# W061X.net
KiCad netlist of a schematic drawn in EAGLE
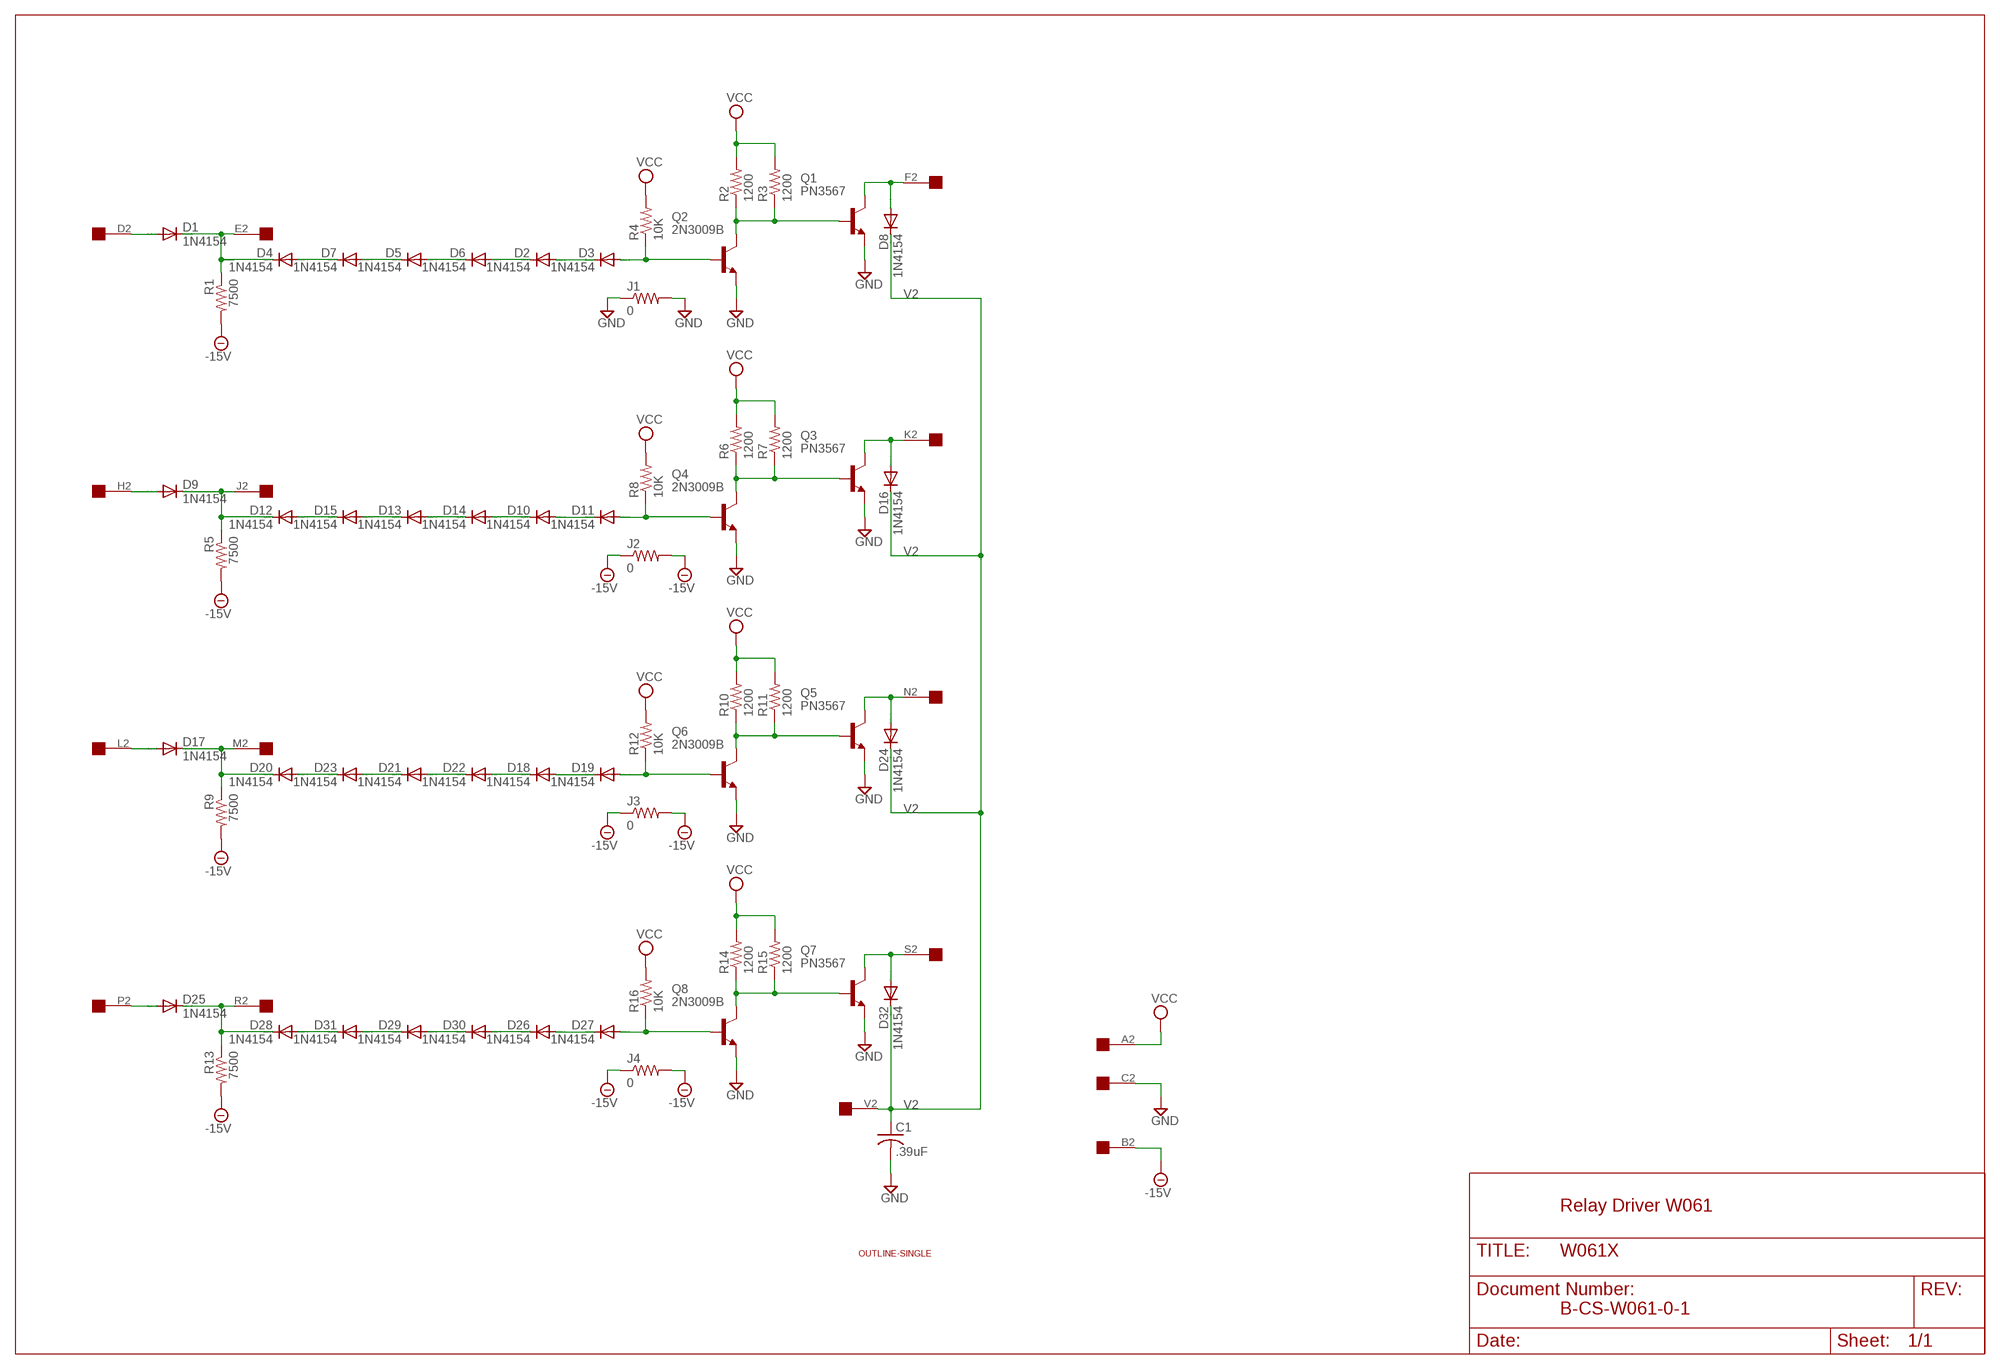
[diagram p0: schematic, sheet 1]

(export (version "E")
  (design (tool "Eeschema 10.0.6"))
  (components
    (comp (ref "C1")
      (value ".39uF")
      (footprint "eagle-import:C375-155X418")
      (libsource (lib "eagle-import") (part "C-US375-155X418"))
    )
    (comp (ref "D1")
      (value "1N4154")
      (footprint "eagle-import:DO35-10")
      (libsource (lib "eagle-import") (part "DIODE-DO35-10"))
    )
    (comp (ref "D2")
      (value "1N4154")
      (footprint "eagle-import:DO35-10")
      (libsource (lib "eagle-import") (part "DIODE-DO35-10"))
    )
    (comp (ref "D3")
      (value "1N4154")
      (footprint "eagle-import:DO35-10")
      (libsource (lib "eagle-import") (part "DIODE-DO35-10"))
    )
    (comp (ref "D4")
      (value "1N4154")
      (footprint "eagle-import:DO35-10")
      (libsource (lib "eagle-import") (part "DIODE-DO35-10"))
    )
    (comp (ref "D5")
      (value "1N4154")
      (footprint "eagle-import:DO35-10")
      (libsource (lib "eagle-import") (part "DIODE-DO35-10"))
    )
    (comp (ref "D6")
      (value "1N4154")
      (footprint "eagle-import:DO35-10")
      (libsource (lib "eagle-import") (part "DIODE-DO35-10"))
    )
    (comp (ref "D7")
      (value "1N4154")
      (footprint "eagle-import:DO35-10")
      (libsource (lib "eagle-import") (part "DIODE-DO35-10"))
    )
    (comp (ref "D8")
      (value "1N4154")
      (footprint "eagle-import:DO35-10")
      (libsource (lib "eagle-import") (part "DIODE-DO35-10"))
    )
    (comp (ref "D9")
      (value "1N4154")
      (footprint "eagle-import:DO35-10")
      (libsource (lib "eagle-import") (part "DIODE-DO35-10"))
    )
    (comp (ref "D10")
      (value "1N4154")
      (footprint "eagle-import:DO35-10")
      (libsource (lib "eagle-import") (part "DIODE-DO35-10"))
    )
    (comp (ref "D11")
      (value "1N4154")
      (footprint "eagle-import:DO35-10")
      (libsource (lib "eagle-import") (part "DIODE-DO35-10"))
    )
    (comp (ref "D12")
      (value "1N4154")
      (footprint "eagle-import:DO35-10")
      (libsource (lib "eagle-import") (part "DIODE-DO35-10"))
    )
    (comp (ref "D13")
      (value "1N4154")
      (footprint "eagle-import:DO35-10")
      (libsource (lib "eagle-import") (part "DIODE-DO35-10"))
    )
    (comp (ref "D14")
      (value "1N4154")
      (footprint "eagle-import:DO35-10")
      (libsource (lib "eagle-import") (part "DIODE-DO35-10"))
    )
    (comp (ref "D15")
      (value "1N4154")
      (footprint "eagle-import:DO35-10")
      (libsource (lib "eagle-import") (part "DIODE-DO35-10"))
    )
    (comp (ref "D16")
      (value "1N4154")
      (footprint "eagle-import:DO35-10")
      (libsource (lib "eagle-import") (part "DIODE-DO35-10"))
    )
    (comp (ref "D17")
      (value "1N4154")
      (footprint "eagle-import:DO35-10")
      (libsource (lib "eagle-import") (part "DIODE-DO35-10"))
    )
    (comp (ref "D18")
      (value "1N4154")
      (footprint "eagle-import:DO35-10")
      (libsource (lib "eagle-import") (part "DIODE-DO35-10"))
    )
    (comp (ref "D19")
      (value "1N4154")
      (footprint "eagle-import:DO35-10")
      (libsource (lib "eagle-import") (part "DIODE-DO35-10"))
    )
    (comp (ref "D20")
      (value "1N4154")
      (footprint "eagle-import:DO35-10")
      (libsource (lib "eagle-import") (part "DIODE-DO35-10"))
    )
    (comp (ref "D21")
      (value "1N4154")
      (footprint "eagle-import:DO35-10")
      (libsource (lib "eagle-import") (part "DIODE-DO35-10"))
    )
    (comp (ref "D22")
      (value "1N4154")
      (footprint "eagle-import:DO35-10")
      (libsource (lib "eagle-import") (part "DIODE-DO35-10"))
    )
    (comp (ref "D23")
      (value "1N4154")
      (footprint "eagle-import:DO35-10")
      (libsource (lib "eagle-import") (part "DIODE-DO35-10"))
    )
    (comp (ref "D24")
      (value "1N4154")
      (footprint "eagle-import:DO35-10")
      (libsource (lib "eagle-import") (part "DIODE-DO35-10"))
    )
    (comp (ref "D25")
      (value "1N4154")
      (footprint "eagle-import:DO35-10")
      (libsource (lib "eagle-import") (part "DIODE-DO35-10"))
    )
    (comp (ref "D26")
      (value "1N4154")
      (footprint "eagle-import:DO35-10")
      (libsource (lib "eagle-import") (part "DIODE-DO35-10"))
    )
    (comp (ref "D27")
      (value "1N4154")
      (footprint "eagle-import:DO35-10")
      (libsource (lib "eagle-import") (part "DIODE-DO35-10"))
    )
    (comp (ref "D28")
      (value "1N4154")
      (footprint "eagle-import:DO35-10")
      (libsource (lib "eagle-import") (part "DIODE-DO35-10"))
    )
    (comp (ref "D29")
      (value "1N4154")
      (footprint "eagle-import:DO35-10")
      (libsource (lib "eagle-import") (part "DIODE-DO35-10"))
    )
    (comp (ref "D30")
      (value "1N4154")
      (footprint "eagle-import:DO35-10")
      (libsource (lib "eagle-import") (part "DIODE-DO35-10"))
    )
    (comp (ref "D31")
      (value "1N4154")
      (footprint "eagle-import:DO35-10")
      (libsource (lib "eagle-import") (part "DIODE-DO35-10"))
    )
    (comp (ref "D32")
      (value "1N4154")
      (footprint "eagle-import:DO35-10")
      (libsource (lib "eagle-import") (part "DIODE-DO35-10"))
    )
    (comp (ref "J1")
      (value "0")
      (footprint "eagle-import:0207_10")
      (libsource (lib "eagle-import") (part "R-US_0207/10"))
    )
    (comp (ref "J2")
      (value "0")
      (footprint "eagle-import:0207_10")
      (libsource (lib "eagle-import") (part "R-US_0207/10"))
    )
    (comp (ref "J3")
      (value "0")
      (footprint "eagle-import:0207_10")
      (libsource (lib "eagle-import") (part "R-US_0207/10"))
    )
    (comp (ref "J4")
      (value "0")
      (footprint "eagle-import:0207_10")
      (libsource (lib "eagle-import") (part "R-US_0207/10"))
    )
    (comp (ref "Q1")
      (value "PN3567")
      (footprint "eagle-import:TO5")
      (libsource (lib "eagle-import") (part "-NPN-TO5"))
    )
    (comp (ref "Q2")
      (value "2N3009B")
      (footprint "eagle-import:TO5")
      (libsource (lib "eagle-import") (part "-NPN-TO5"))
    )
    (comp (ref "Q3")
      (value "PN3567")
      (footprint "eagle-import:TO5")
      (libsource (lib "eagle-import") (part "-NPN-TO5"))
    )
    (comp (ref "Q4")
      (value "2N3009B")
      (footprint "eagle-import:TO5")
      (libsource (lib "eagle-import") (part "-NPN-TO5"))
    )
    (comp (ref "Q5")
      (value "PN3567")
      (footprint "eagle-import:TO5")
      (libsource (lib "eagle-import") (part "-NPN-TO5"))
    )
    (comp (ref "Q6")
      (value "2N3009B")
      (footprint "eagle-import:TO5")
      (libsource (lib "eagle-import") (part "-NPN-TO5"))
    )
    (comp (ref "Q7")
      (value "PN3567")
      (footprint "eagle-import:TO5")
      (libsource (lib "eagle-import") (part "-NPN-TO5"))
    )
    (comp (ref "Q8")
      (value "2N3009B")
      (footprint "eagle-import:TO5")
      (libsource (lib "eagle-import") (part "-NPN-TO5"))
    )
    (comp (ref "R1")
      (value "7500")
      (footprint "eagle-import:0207_10")
      (libsource (lib "eagle-import") (part "R-US_0207/10"))
    )
    (comp (ref "R2")
      (value "1200")
      (footprint "eagle-import:0207_10")
      (libsource (lib "eagle-import") (part "R-US_0207/10"))
    )
    (comp (ref "R3")
      (value "1200")
      (footprint "eagle-import:0207_10")
      (libsource (lib "eagle-import") (part "R-US_0207/10"))
    )
    (comp (ref "R4")
      (value "10K")
      (footprint "eagle-import:0207_10")
      (libsource (lib "eagle-import") (part "R-US_0207/10"))
    )
    (comp (ref "R5")
      (value "7500")
      (footprint "eagle-import:0207_10")
      (libsource (lib "eagle-import") (part "R-US_0207/10"))
    )
    (comp (ref "R6")
      (value "1200")
      (footprint "eagle-import:0207_10")
      (libsource (lib "eagle-import") (part "R-US_0207/10"))
    )
    (comp (ref "R7")
      (value "1200")
      (footprint "eagle-import:0207_10")
      (libsource (lib "eagle-import") (part "R-US_0207/10"))
    )
    (comp (ref "R8")
      (value "10K")
      (footprint "eagle-import:0207_10")
      (libsource (lib "eagle-import") (part "R-US_0207/10"))
    )
    (comp (ref "R9")
      (value "7500")
      (footprint "eagle-import:0207_10")
      (libsource (lib "eagle-import") (part "R-US_0207/10"))
    )
    (comp (ref "R10")
      (value "1200")
      (footprint "eagle-import:0207_10")
      (libsource (lib "eagle-import") (part "R-US_0207/10"))
    )
    (comp (ref "R11")
      (value "1200")
      (footprint "eagle-import:0207_10")
      (libsource (lib "eagle-import") (part "R-US_0207/10"))
    )
    (comp (ref "R12")
      (value "10K")
      (footprint "eagle-import:0207_10")
      (libsource (lib "eagle-import") (part "R-US_0207/10"))
    )
    (comp (ref "R13")
      (value "7500")
      (footprint "eagle-import:0207_10")
      (libsource (lib "eagle-import") (part "R-US_0207/10"))
    )
    (comp (ref "R14")
      (value "1200")
      (footprint "eagle-import:0207_10")
      (libsource (lib "eagle-import") (part "R-US_0207/10"))
    )
    (comp (ref "R15")
      (value "1200")
      (footprint "eagle-import:0207_10")
      (libsource (lib "eagle-import") (part "R-US_0207/10"))
    )
    (comp (ref "R16")
      (value "10K")
      (footprint "eagle-import:0207_10")
      (libsource (lib "eagle-import") (part "R-US_0207/10"))
    )
    (comp (ref "U$1")
      (value "OUTLINE-SINGLE")
      (footprint "eagle-import:SINGLE")
      (libsource (lib "eagle-import") (part "OUTLINE-SINGLE"))
    )
    (comp (ref "U$2")
      (value "EDGE-1")
      (footprint "eagle-import:EDGE-CON1")
      (libsource (lib "eagle-import") (part "EDGE-1"))
    )
  )
  (nets
    (net (code "1") (name "-15V") (class "Default")
      (node (ref "J2") (pin "1") (pinfunction "1_1") (pintype "passive"))
      (node (ref "J2") (pin "2") (pinfunction "2_2") (pintype "passive"))
      (node (ref "J3") (pin "1") (pinfunction "1_1") (pintype "passive"))
      (node (ref "J3") (pin "2") (pinfunction "2_2") (pintype "passive"))
      (node (ref "J4") (pin "1") (pinfunction "1_1") (pintype "passive"))
      (node (ref "J4") (pin "2") (pinfunction "2_2") (pintype "passive"))
      (node (ref "R1") (pin "2") (pinfunction "2_2") (pintype "passive"))
      (node (ref "R13") (pin "2") (pinfunction "2_2") (pintype "passive"))
      (node (ref "R5") (pin "2") (pinfunction "2_2") (pintype "passive"))
      (node (ref "R9") (pin "2") (pinfunction "2_2") (pintype "passive"))
      (node (ref "U$2") (pin "B2") (pinfunction "1_B2") (pintype "bidirectional"))
    )
    (net (code "2") (name "/V2") (class "Default")
      (node (ref "C1") (pin "1") (pinfunction "1_1") (pintype "passive"))
      (node (ref "D16") (pin "C") (pinfunction "C_C") (pintype "passive"))
      (node (ref "D24") (pin "C") (pinfunction "C_C") (pintype "passive"))
      (node (ref "D32") (pin "C") (pinfunction "C_C") (pintype "passive"))
      (node (ref "D8") (pin "C") (pinfunction "C_C") (pintype "passive"))
      (node (ref "U$2") (pin "V2") (pinfunction "1_V2") (pintype "bidirectional"))
    )
    (net (code "3") (name "GND") (class "Default")
      (node (ref "C1") (pin "2") (pinfunction "2_2") (pintype "passive"))
      (node (ref "J1") (pin "1") (pinfunction "1_1") (pintype "passive"))
      (node (ref "J1") (pin "2") (pinfunction "2_2") (pintype "passive"))
      (node (ref "Q1") (pin "1") (pinfunction "E_1") (pintype "passive"))
      (node (ref "Q2") (pin "1") (pinfunction "E_1") (pintype "passive"))
      (node (ref "Q3") (pin "1") (pinfunction "E_1") (pintype "passive"))
      (node (ref "Q4") (pin "1") (pinfunction "E_1") (pintype "passive"))
      (node (ref "Q5") (pin "1") (pinfunction "E_1") (pintype "passive"))
      (node (ref "Q6") (pin "1") (pinfunction "E_1") (pintype "passive"))
      (node (ref "Q7") (pin "1") (pinfunction "E_1") (pintype "passive"))
      (node (ref "Q8") (pin "1") (pinfunction "E_1") (pintype "passive"))
      (node (ref "U$2") (pin "C2") (pinfunction "1_C2") (pintype "bidirectional"))
    )
    (net (code "4") (name "Net-(D2-PadA)") (class "Default")
      (node (ref "D2") (pin "A") (pinfunction "A_A") (pintype "passive"))
      (node (ref "D3") (pin "C") (pinfunction "C_C") (pintype "passive"))
    )
    (net (code "5") (name "Net-(D2-PadC)") (class "Default")
      (node (ref "D2") (pin "C") (pinfunction "C_C") (pintype "passive"))
      (node (ref "D6") (pin "A") (pinfunction "A_A") (pintype "passive"))
    )
    (net (code "6") (name "Net-(D4-PadA)") (class "Default")
      (node (ref "D4") (pin "A") (pinfunction "A_A") (pintype "passive"))
      (node (ref "D7") (pin "C") (pinfunction "C_C") (pintype "passive"))
    )
    (net (code "7") (name "Net-(D5-PadA)") (class "Default")
      (node (ref "D5") (pin "A") (pinfunction "A_A") (pintype "passive"))
      (node (ref "D6") (pin "C") (pinfunction "C_C") (pintype "passive"))
    )
    (net (code "8") (name "Net-(D5-PadC)") (class "Default")
      (node (ref "D5") (pin "C") (pinfunction "C_C") (pintype "passive"))
      (node (ref "D7") (pin "A") (pinfunction "A_A") (pintype "passive"))
    )
    (net (code "9") (name "Net-(D10-PadA)") (class "Default")
      (node (ref "D10") (pin "A") (pinfunction "A_A") (pintype "passive"))
      (node (ref "D11") (pin "C") (pinfunction "C_C") (pintype "passive"))
    )
    (net (code "10") (name "Net-(D10-PadC)") (class "Default")
      (node (ref "D10") (pin "C") (pinfunction "C_C") (pintype "passive"))
      (node (ref "D14") (pin "A") (pinfunction "A_A") (pintype "passive"))
    )
    (net (code "11") (name "Net-(D12-PadA)") (class "Default")
      (node (ref "D12") (pin "A") (pinfunction "A_A") (pintype "passive"))
      (node (ref "D15") (pin "C") (pinfunction "C_C") (pintype "passive"))
    )
    (net (code "12") (name "Net-(D13-PadA)") (class "Default")
      (node (ref "D13") (pin "A") (pinfunction "A_A") (pintype "passive"))
      (node (ref "D14") (pin "C") (pinfunction "C_C") (pintype "passive"))
    )
    (net (code "13") (name "Net-(D13-PadC)") (class "Default")
      (node (ref "D13") (pin "C") (pinfunction "C_C") (pintype "passive"))
      (node (ref "D15") (pin "A") (pinfunction "A_A") (pintype "passive"))
    )
    (net (code "14") (name "Net-(D18-PadA)") (class "Default")
      (node (ref "D18") (pin "A") (pinfunction "A_A") (pintype "passive"))
      (node (ref "D19") (pin "C") (pinfunction "C_C") (pintype "passive"))
    )
    (net (code "15") (name "Net-(D18-PadC)") (class "Default")
      (node (ref "D18") (pin "C") (pinfunction "C_C") (pintype "passive"))
      (node (ref "D22") (pin "A") (pinfunction "A_A") (pintype "passive"))
    )
    (net (code "16") (name "Net-(D20-PadA)") (class "Default")
      (node (ref "D20") (pin "A") (pinfunction "A_A") (pintype "passive"))
      (node (ref "D23") (pin "C") (pinfunction "C_C") (pintype "passive"))
    )
    (net (code "17") (name "Net-(D21-PadA)") (class "Default")
      (node (ref "D21") (pin "A") (pinfunction "A_A") (pintype "passive"))
      (node (ref "D22") (pin "C") (pinfunction "C_C") (pintype "passive"))
    )
    (net (code "18") (name "Net-(D21-PadC)") (class "Default")
      (node (ref "D21") (pin "C") (pinfunction "C_C") (pintype "passive"))
      (node (ref "D23") (pin "A") (pinfunction "A_A") (pintype "passive"))
    )
    (net (code "19") (name "Net-(D26-PadA)") (class "Default")
      (node (ref "D26") (pin "A") (pinfunction "A_A") (pintype "passive"))
      (node (ref "D27") (pin "C") (pinfunction "C_C") (pintype "passive"))
    )
    (net (code "20") (name "Net-(D26-PadC)") (class "Default")
      (node (ref "D26") (pin "C") (pinfunction "C_C") (pintype "passive"))
      (node (ref "D30") (pin "A") (pinfunction "A_A") (pintype "passive"))
    )
    (net (code "21") (name "Net-(D28-PadA)") (class "Default")
      (node (ref "D28") (pin "A") (pinfunction "A_A") (pintype "passive"))
      (node (ref "D31") (pin "C") (pinfunction "C_C") (pintype "passive"))
    )
    (net (code "22") (name "Net-(D29-PadA)") (class "Default")
      (node (ref "D29") (pin "A") (pinfunction "A_A") (pintype "passive"))
      (node (ref "D30") (pin "C") (pinfunction "C_C") (pintype "passive"))
    )
    (net (code "23") (name "Net-(D29-PadC)") (class "Default")
      (node (ref "D29") (pin "C") (pinfunction "C_C") (pintype "passive"))
      (node (ref "D31") (pin "A") (pinfunction "A_A") (pintype "passive"))
    )
    (net (code "24") (name "Net-(Q1-B)") (class "Default")
      (node (ref "Q1") (pin "2") (pinfunction "B_2") (pintype "passive"))
      (node (ref "Q2") (pin "3") (pinfunction "C_3") (pintype "passive"))
      (node (ref "R2") (pin "1") (pinfunction "1_1") (pintype "passive"))
      (node (ref "R3") (pin "1") (pinfunction "1_1") (pintype "passive"))
    )
    (net (code "25") (name "Net-(Q1-C)") (class "Default")
      (node (ref "D8") (pin "A") (pinfunction "A_A") (pintype "passive"))
      (node (ref "Q1") (pin "3") (pinfunction "C_3") (pintype "passive"))
      (node (ref "U$2") (pin "F2") (pinfunction "1_F2") (pintype "bidirectional"))
    )
    (net (code "26") (name "Net-(Q2-B)") (class "Default")
      (node (ref "D3") (pin "A") (pinfunction "A_A") (pintype "passive"))
      (node (ref "Q2") (pin "2") (pinfunction "B_2") (pintype "passive"))
      (node (ref "R4") (pin "1") (pinfunction "1_1") (pintype "passive"))
    )
    (net (code "27") (name "Net-(Q3-B)") (class "Default")
      (node (ref "Q3") (pin "2") (pinfunction "B_2") (pintype "passive"))
      (node (ref "Q4") (pin "3") (pinfunction "C_3") (pintype "passive"))
      (node (ref "R6") (pin "1") (pinfunction "1_1") (pintype "passive"))
      (node (ref "R7") (pin "1") (pinfunction "1_1") (pintype "passive"))
    )
    (net (code "28") (name "Net-(Q3-C)") (class "Default")
      (node (ref "D16") (pin "A") (pinfunction "A_A") (pintype "passive"))
      (node (ref "Q3") (pin "3") (pinfunction "C_3") (pintype "passive"))
      (node (ref "U$2") (pin "K2") (pinfunction "1_K2") (pintype "bidirectional"))
    )
    (net (code "29") (name "Net-(Q4-B)") (class "Default")
      (node (ref "D11") (pin "A") (pinfunction "A_A") (pintype "passive"))
      (node (ref "Q4") (pin "2") (pinfunction "B_2") (pintype "passive"))
      (node (ref "R8") (pin "1") (pinfunction "1_1") (pintype "passive"))
    )
    (net (code "30") (name "Net-(Q5-B)") (class "Default")
      (node (ref "Q5") (pin "2") (pinfunction "B_2") (pintype "passive"))
      (node (ref "Q6") (pin "3") (pinfunction "C_3") (pintype "passive"))
      (node (ref "R10") (pin "1") (pinfunction "1_1") (pintype "passive"))
      (node (ref "R11") (pin "1") (pinfunction "1_1") (pintype "passive"))
    )
    (net (code "31") (name "Net-(Q5-C)") (class "Default")
      (node (ref "D24") (pin "A") (pinfunction "A_A") (pintype "passive"))
      (node (ref "Q5") (pin "3") (pinfunction "C_3") (pintype "passive"))
      (node (ref "U$2") (pin "N2") (pinfunction "1_N2") (pintype "bidirectional"))
    )
    (net (code "32") (name "Net-(Q6-B)") (class "Default")
      (node (ref "D19") (pin "A") (pinfunction "A_A") (pintype "passive"))
      (node (ref "Q6") (pin "2") (pinfunction "B_2") (pintype "passive"))
      (node (ref "R12") (pin "1") (pinfunction "1_1") (pintype "passive"))
    )
    (net (code "33") (name "Net-(Q7-B)") (class "Default")
      (node (ref "Q7") (pin "2") (pinfunction "B_2") (pintype "passive"))
      (node (ref "Q8") (pin "3") (pinfunction "C_3") (pintype "passive"))
      (node (ref "R14") (pin "1") (pinfunction "1_1") (pintype "passive"))
      (node (ref "R15") (pin "1") (pinfunction "1_1") (pintype "passive"))
    )
    (net (code "34") (name "Net-(Q7-C)") (class "Default")
      (node (ref "D32") (pin "A") (pinfunction "A_A") (pintype "passive"))
      (node (ref "Q7") (pin "3") (pinfunction "C_3") (pintype "passive"))
      (node (ref "U$2") (pin "S2") (pinfunction "1_S2") (pintype "bidirectional"))
    )
    (net (code "35") (name "Net-(Q8-B)") (class "Default")
      (node (ref "D27") (pin "A") (pinfunction "A_A") (pintype "passive"))
      (node (ref "Q8") (pin "2") (pinfunction "B_2") (pintype "passive"))
      (node (ref "R16") (pin "1") (pinfunction "1_1") (pintype "passive"))
    )
    (net (code "36") (name "Net-(U$2D-1)") (class "Default")
      (node (ref "D1") (pin "A") (pinfunction "A_A") (pintype "passive"))
      (node (ref "U$2") (pin "D2") (pinfunction "1_D2") (pintype "bidirectional"))
    )
    (net (code "37") (name "Net-(U$2E-1)") (class "Default")
      (node (ref "D1") (pin "C") (pinfunction "C_C") (pintype "passive"))
      (node (ref "D4") (pin "C") (pinfunction "C_C") (pintype "passive"))
      (node (ref "R1") (pin "1") (pinfunction "1_1") (pintype "passive"))
      (node (ref "U$2") (pin "E2") (pinfunction "1_E2") (pintype "bidirectional"))
    )
    (net (code "38") (name "Net-(U$2G-1)") (class "Default")
      (node (ref "D9") (pin "A") (pinfunction "A_A") (pintype "passive"))
      (node (ref "U$2") (pin "H2") (pinfunction "1_H2") (pintype "bidirectional"))
    )
    (net (code "39") (name "Net-(U$2H-1)") (class "Default")
      (node (ref "D12") (pin "C") (pinfunction "C_C") (pintype "passive"))
      (node (ref "D9") (pin "C") (pinfunction "C_C") (pintype "passive"))
      (node (ref "R5") (pin "1") (pinfunction "1_1") (pintype "passive"))
      (node (ref "U$2") (pin "J2") (pinfunction "1_J2") (pintype "bidirectional"))
    )
    (net (code "40") (name "Net-(U$2J-1)") (class "Default")
      (node (ref "D17") (pin "A") (pinfunction "A_A") (pintype "passive"))
      (node (ref "U$2") (pin "L2") (pinfunction "1_L2") (pintype "bidirectional"))
    )
    (net (code "41") (name "Net-(U$2K-1)") (class "Default")
      (node (ref "D17") (pin "C") (pinfunction "C_C") (pintype "passive"))
      (node (ref "D20") (pin "C") (pinfunction "C_C") (pintype "passive"))
      (node (ref "R9") (pin "1") (pinfunction "1_1") (pintype "passive"))
      (node (ref "U$2") (pin "M2") (pinfunction "1_M2") (pintype "bidirectional"))
    )
    (net (code "42") (name "Net-(U$2M-1)") (class "Default")
      (node (ref "D25") (pin "A") (pinfunction "A_A") (pintype "passive"))
      (node (ref "U$2") (pin "P2") (pinfunction "1_P2") (pintype "bidirectional"))
    )
    (net (code "43") (name "Net-(U$2N-1)") (class "Default")
      (node (ref "D25") (pin "C") (pinfunction "C_C") (pintype "passive"))
      (node (ref "D28") (pin "C") (pinfunction "C_C") (pintype "passive"))
      (node (ref "R13") (pin "1") (pinfunction "1_1") (pintype "passive"))
      (node (ref "U$2") (pin "R2") (pinfunction "1_R2") (pintype "bidirectional"))
    )
    (net (code "44") (name "VCC") (class "Default")
      (node (ref "R10") (pin "2") (pinfunction "2_2") (pintype "passive"))
      (node (ref "R11") (pin "2") (pinfunction "2_2") (pintype "passive"))
      (node (ref "R12") (pin "2") (pinfunction "2_2") (pintype "passive"))
      (node (ref "R14") (pin "2") (pinfunction "2_2") (pintype "passive"))
      (node (ref "R15") (pin "2") (pinfunction "2_2") (pintype "passive"))
      (node (ref "R16") (pin "2") (pinfunction "2_2") (pintype "passive"))
      (node (ref "R2") (pin "2") (pinfunction "2_2") (pintype "passive"))
      (node (ref "R3") (pin "2") (pinfunction "2_2") (pintype "passive"))
      (node (ref "R4") (pin "2") (pinfunction "2_2") (pintype "passive"))
      (node (ref "R6") (pin "2") (pinfunction "2_2") (pintype "passive"))
      (node (ref "R7") (pin "2") (pinfunction "2_2") (pintype "passive"))
      (node (ref "R8") (pin "2") (pinfunction "2_2") (pintype "passive"))
      (node (ref "U$2") (pin "A2") (pinfunction "1_A2") (pintype "bidirectional"))
    )
  )
)
